# Channel_A.net
KiCad netlist of a schematic drawn in Altium Designer
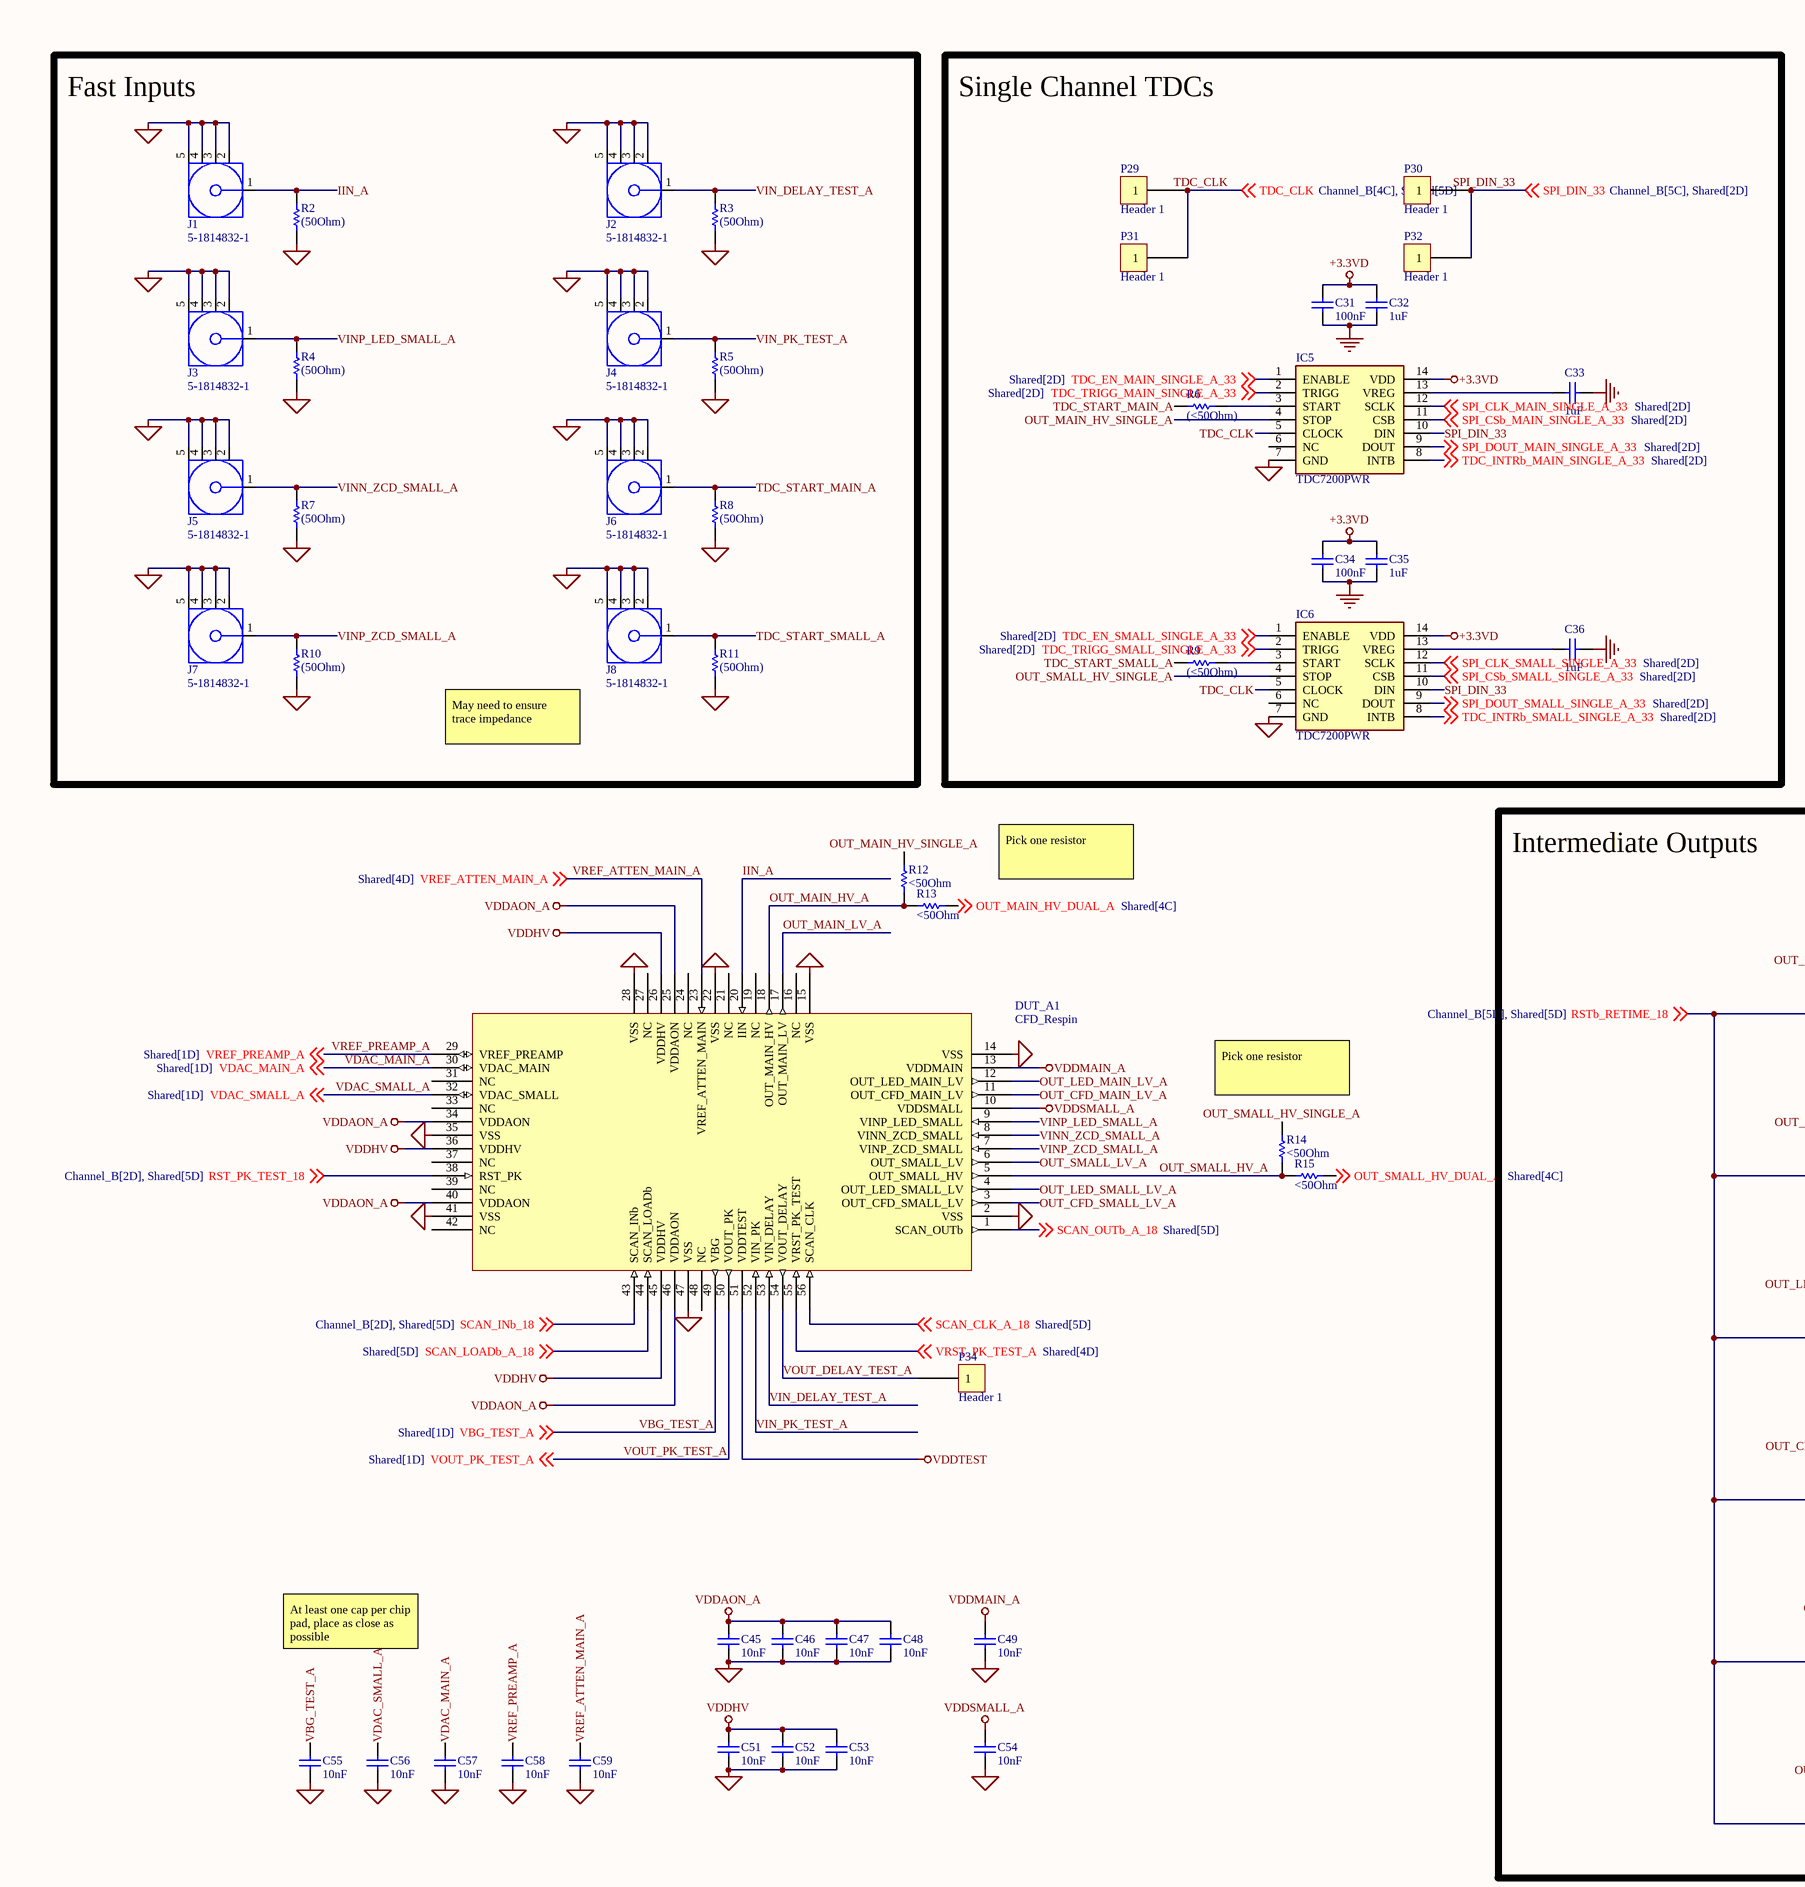
[diagram p0: Channel_A.SchDoc, left]
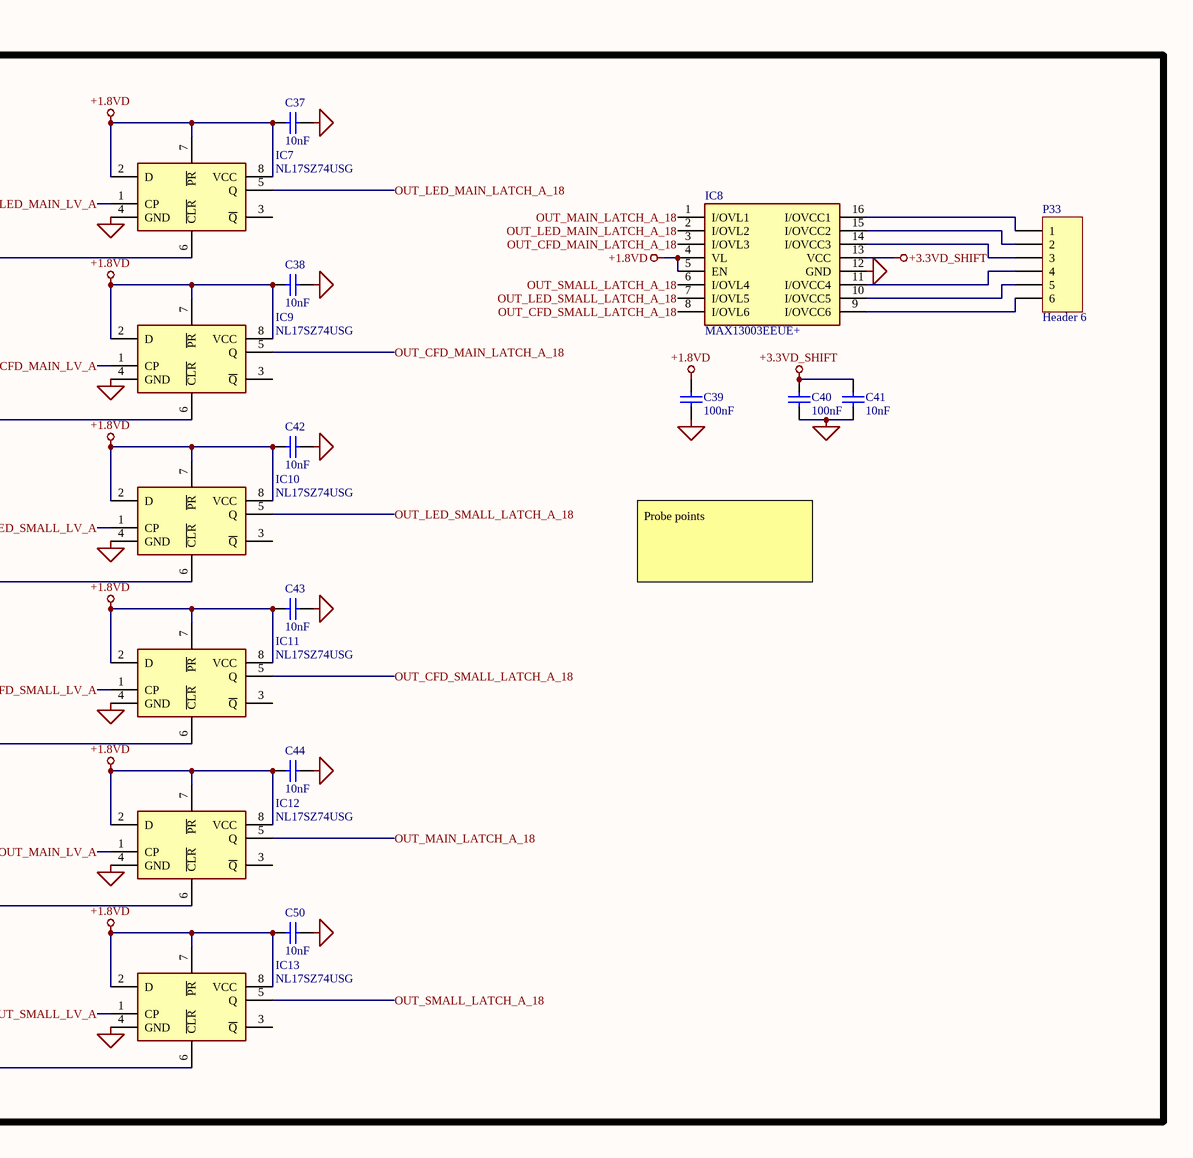
[diagram p1: Channel_A.SchDoc, right]

(export (version "E")
  (design (tool "Eeschema 10.0.6"))
  (components
    (comp (ref "C31")
      (value "100nF")
      (footprint "CAPC1608X90X35ML10T15")
      (description "0603")
      (fields (field (name "MANUFACTURER") "Murata"))
      (libsource (lib "Altium Content Vault") (part "CAP-NP-2"))
    )
    (comp (ref "C32")
      (value "1uF")
      (footprint "CAPC1608X90X35ML10T15")
      (description "0603")
      (fields (field (name "MANUFACTURER") "Murata"))
      (libsource (lib "Altium Content Vault") (part "CAP-NP-2"))
    )
    (comp (ref "C33")
      (value "1uF")
      (footprint "CAPC1608X90X35ML10T15")
      (description "0603")
      (fields (field (name "MANUFACTURER") "Murata"))
      (libsource (lib "Altium Content Vault") (part "CAP-NP-2"))
    )
    (comp (ref "C34")
      (value "100nF")
      (footprint "CAPC1608X90X35ML10T15")
      (description "0603")
      (fields (field (name "MANUFACTURER") "Murata"))
      (libsource (lib "Altium Content Vault") (part "CAP-NP-2"))
    )
    (comp (ref "C35")
      (value "1uF")
      (footprint "CAPC1608X90X35ML10T15")
      (description "0603")
      (fields (field (name "MANUFACTURER") "Murata"))
      (libsource (lib "Altium Content Vault") (part "CAP-NP-2"))
    )
    (comp (ref "C36")
      (value "1uF")
      (footprint "CAPC1608X90X35ML10T15")
      (description "0603")
      (fields (field (name "MANUFACTURER") "Murata"))
      (libsource (lib "Altium Content Vault") (part "CAP-NP-2"))
    )
    (comp (ref "C37")
      (value "10nF")
      (footprint "CAPC1608X90X35ML10T15")
      (description "0603")
      (fields (field (name "MANUFACTURER") "Murata"))
      (libsource (lib "Altium Content Vault") (part "CAP-NP-2"))
    )
    (comp (ref "C38")
      (value "10nF")
      (footprint "CAPC1608X90X35ML10T15")
      (description "0603")
      (fields (field (name "MANUFACTURER") "Murata"))
      (libsource (lib "Altium Content Vault") (part "CAP-NP-2"))
    )
    (comp (ref "C39")
      (value "100nF")
      (footprint "CAPC1608X90X35ML10T15")
      (description "0603")
      (fields (field (name "MANUFACTURER") "Murata"))
      (libsource (lib "Altium Content Vault") (part "CAP-NP-2"))
    )
    (comp (ref "C40")
      (value "100nF")
      (footprint "CAPC1608X90X35ML10T15")
      (description "0603")
      (fields (field (name "MANUFACTURER") "Murata"))
      (libsource (lib "Altium Content Vault") (part "CAP-NP-2"))
    )
    (comp (ref "C41")
      (value "10nF")
      (footprint "CAPC1608X90X35ML10T15")
      (description "0603")
      (fields (field (name "MANUFACTURER") "Murata"))
      (libsource (lib "Altium Content Vault") (part "CAP-NP-2"))
    )
    (comp (ref "C42")
      (value "10nF")
      (footprint "CAPC1608X90X35ML10T15")
      (description "0603")
      (fields (field (name "MANUFACTURER") "Murata"))
      (libsource (lib "Altium Content Vault") (part "CAP-NP-2"))
    )
    (comp (ref "C43")
      (value "10nF")
      (footprint "CAPC1608X90X35ML10T15")
      (description "0603")
      (fields (field (name "MANUFACTURER") "Murata"))
      (libsource (lib "Altium Content Vault") (part "CAP-NP-2"))
    )
    (comp (ref "C44")
      (value "10nF")
      (footprint "CAPC1608X90X35ML10T15")
      (description "0603")
      (fields (field (name "MANUFACTURER") "Murata"))
      (libsource (lib "Altium Content Vault") (part "CAP-NP-2"))
    )
    (comp (ref "C45")
      (value "10nF")
      (footprint "CAPC1608X90X35ML10T15")
      (description "0603")
      (fields (field (name "MANUFACTURER") "Murata"))
      (libsource (lib "Altium Content Vault") (part "CAP-NP-2"))
    )
    (comp (ref "C46")
      (value "10nF")
      (footprint "CAPC1608X90X35ML10T15")
      (description "0603")
      (fields (field (name "MANUFACTURER") "Murata"))
      (libsource (lib "Altium Content Vault") (part "CAP-NP-2"))
    )
    (comp (ref "C47")
      (value "10nF")
      (footprint "CAPC1608X90X35ML10T15")
      (description "0603")
      (fields (field (name "MANUFACTURER") "Murata"))
      (libsource (lib "Altium Content Vault") (part "CAP-NP-2"))
    )
    (comp (ref "C48")
      (value "10nF")
      (footprint "CAPC1608X90X35ML10T15")
      (description "0603")
      (fields (field (name "MANUFACTURER") "Murata"))
      (libsource (lib "Altium Content Vault") (part "CAP-NP-2"))
    )
    (comp (ref "C49")
      (value "10nF")
      (footprint "CAPC1608X90X35ML10T15")
      (description "0603")
      (fields (field (name "MANUFACTURER") "Murata"))
      (libsource (lib "Altium Content Vault") (part "CAP-NP-2"))
    )
    (comp (ref "C50")
      (value "10nF")
      (footprint "CAPC1608X90X35ML10T15")
      (description "0603")
      (fields (field (name "MANUFACTURER") "Murata"))
      (libsource (lib "Altium Content Vault") (part "CAP-NP-2"))
    )
    (comp (ref "C51")
      (value "10nF")
      (footprint "CAPC1608X90X35ML10T15")
      (description "0603")
      (fields (field (name "MANUFACTURER") "Murata"))
      (libsource (lib "Altium Content Vault") (part "CAP-NP-2"))
    )
    (comp (ref "C52")
      (value "10nF")
      (footprint "CAPC1608X90X35ML10T15")
      (description "0603")
      (fields (field (name "MANUFACTURER") "Murata"))
      (libsource (lib "Altium Content Vault") (part "CAP-NP-2"))
    )
    (comp (ref "C53")
      (value "10nF")
      (footprint "CAPC1608X90X35ML10T15")
      (description "0603")
      (fields (field (name "MANUFACTURER") "Murata"))
      (libsource (lib "Altium Content Vault") (part "CAP-NP-2"))
    )
    (comp (ref "C54")
      (value "10nF")
      (footprint "CAPC1608X90X35ML10T15")
      (description "0603")
      (fields (field (name "MANUFACTURER") "Murata"))
      (libsource (lib "Altium Content Vault") (part "CAP-NP-2"))
    )
    (comp (ref "C55")
      (value "10nF")
      (footprint "CAPC1608X90X35ML10T15")
      (description "0603")
      (fields (field (name "MANUFACTURER") "Murata"))
      (libsource (lib "Altium Content Vault") (part "CAP-NP-2"))
    )
    (comp (ref "C56")
      (value "10nF")
      (footprint "CAPC1608X90X35ML10T15")
      (description "0603")
      (fields (field (name "MANUFACTURER") "Murata"))
      (libsource (lib "Altium Content Vault") (part "CAP-NP-2"))
    )
    (comp (ref "C57")
      (value "10nF")
      (footprint "CAPC1608X90X35ML10T15")
      (description "0603")
      (fields (field (name "MANUFACTURER") "Murata"))
      (libsource (lib "Altium Content Vault") (part "CAP-NP-2"))
    )
    (comp (ref "C58")
      (value "10nF")
      (footprint "CAPC1608X90X35ML10T15")
      (description "0603")
      (fields (field (name "MANUFACTURER") "Murata"))
      (libsource (lib "Altium Content Vault") (part "CAP-NP-2"))
    )
    (comp (ref "C59")
      (value "10nF")
      (footprint "CAPC1608X90X35ML10T15")
      (description "0603")
      (fields (field (name "MANUFACTURER") "Murata"))
      (libsource (lib "Altium Content Vault") (part "CAP-NP-2"))
    )
    (comp (ref "DUT_A1")
      (value "CFD_Respin")
      (footprint "QFN50P800X800X80_HS-57N_WIDEVIAS")
      (libsource (lib "intlib") (part "CFD_Respin"))
    )
    (comp (ref "IC5")
      (value "TDC7200PWR")
      (footprint "SamacSys:SOP65P640X120-14N")
      (description "Integrated Circuit")
      (libsource (lib "*") (part "TDC7200PWR"))
    )
    (comp (ref "IC6")
      (value "TDC7200PWR")
      (footprint "SamacSys:SOP65P640X120-14N")
      (description "Integrated Circuit")
      (libsource (lib "*") (part "TDC7200PWR"))
    )
    (comp (ref "IC7")
      (value "NL17SZ74USG")
      (footprint "SamacSys:SOP50P310X90-8N")
      (description "Flip Flops 1.65-5.5V CMOS Single D-Type")
      (libsource (lib "SamacSys") (part "NL17SZ74USG"))
    )
    (comp (ref "IC8")
      (value "MAX13003EEUE+")
      (footprint "SamacSys:SOP65P640X110-16N")
      (description "Integrated Circuit")
      (libsource (lib "*") (part "MAX13003EEUE+"))
    )
    (comp (ref "IC9")
      (value "NL17SZ74USG")
      (footprint "SamacSys:SOP50P310X90-8N")
      (description "Flip Flops 1.65-5.5V CMOS Single D-Type")
      (libsource (lib "SamacSys") (part "NL17SZ74USG"))
    )
    (comp (ref "IC10")
      (value "NL17SZ74USG")
      (footprint "SamacSys:SOP50P310X90-8N")
      (description "Flip Flops 1.65-5.5V CMOS Single D-Type")
      (libsource (lib "SamacSys") (part "NL17SZ74USG"))
    )
    (comp (ref "IC11")
      (value "NL17SZ74USG")
      (footprint "SamacSys:SOP50P310X90-8N")
      (description "Flip Flops 1.65-5.5V CMOS Single D-Type")
      (libsource (lib "SamacSys") (part "NL17SZ74USG"))
    )
    (comp (ref "IC12")
      (value "NL17SZ74USG")
      (footprint "SamacSys:SOP50P310X90-8N")
      (description "Flip Flops 1.65-5.5V CMOS Single D-Type")
      (libsource (lib "SamacSys") (part "NL17SZ74USG"))
    )
    (comp (ref "IC13")
      (value "NL17SZ74USG")
      (footprint "SamacSys:SOP50P310X90-8N")
      (description "Flip Flops 1.65-5.5V CMOS Single D-Type")
      (libsource (lib "SamacSys") (part "NL17SZ74USG"))
    )
    (comp (ref "J1")
      (value "5-1814832-1")
      (footprint "TECO-5-1814832-1_V")
      (fields (field (name "MANUFACTURER") "TE Connectivity"))
      (libsource (lib "Altium Content Vault") (part "CN-S-4F-RF5"))
    )
    (comp (ref "J2")
      (value "5-1814832-1")
      (footprint "TECO-5-1814832-1_V")
      (fields (field (name "MANUFACTURER") "TE Connectivity"))
      (libsource (lib "Altium Content Vault") (part "CN-S-4F-RF5"))
    )
    (comp (ref "J3")
      (value "5-1814832-1")
      (footprint "TECO-5-1814832-1_V")
      (fields (field (name "MANUFACTURER") "TE Connectivity"))
      (libsource (lib "Altium Content Vault") (part "CN-S-4F-RF5"))
    )
    (comp (ref "J4")
      (value "5-1814832-1")
      (footprint "TECO-5-1814832-1_V")
      (fields (field (name "MANUFACTURER") "TE Connectivity"))
      (libsource (lib "Altium Content Vault") (part "CN-S-4F-RF5"))
    )
    (comp (ref "J5")
      (value "5-1814832-1")
      (footprint "TECO-5-1814832-1_V")
      (fields (field (name "MANUFACTURER") "TE Connectivity"))
      (libsource (lib "Altium Content Vault") (part "CN-S-4F-RF5"))
    )
    (comp (ref "J6")
      (value "5-1814832-1")
      (footprint "TECO-5-1814832-1_V")
      (fields (field (name "MANUFACTURER") "TE Connectivity"))
      (libsource (lib "Altium Content Vault") (part "CN-S-4F-RF5"))
    )
    (comp (ref "J7")
      (value "5-1814832-1")
      (footprint "TECO-5-1814832-1_V")
      (fields (field (name "MANUFACTURER") "TE Connectivity"))
      (libsource (lib "Altium Content Vault") (part "CN-S-4F-RF5"))
    )
    (comp (ref "J8")
      (value "5-1814832-1")
      (footprint "TECO-5-1814832-1_V")
      (fields (field (name "MANUFACTURER") "TE Connectivity"))
      (libsource (lib "Altium Content Vault") (part "CN-S-4F-RF5"))
    )
    (comp (ref "P29") (value "Header 1") (footprint "Header1") (libsource (lib "intlib") (part "Header 1")))
    (comp (ref "P30") (value "Header 1") (footprint "Header1") (libsource (lib "intlib") (part "Header 1")))
    (comp (ref "P31") (value "Header 1") (footprint "Header1") (libsource (lib "intlib") (part "Header 1")))
    (comp (ref "P32") (value "Header 1") (footprint "Header1") (libsource (lib "intlib") (part "Header 1")))
    (comp (ref "P33")
      (value "Header 6")
      (footprint "HDR1X6")
      (description "Header, 6-Pin")
      (fields (field (name "PUBLISHER") "Altium Limited"))
      (libsource (lib "Miscellaneous Connectors") (part "Header 6"))
    )
    (comp (ref "P34") (value "Header 1") (footprint "Header1") (libsource (lib "") (part "Header 1_1")))
    (comp (ref "R2")
      (value "(50Ohm)")
      (footprint "RESC1609X50X30NL8T20")
      (description "0603")
      (fields (field (name "MANUFACTURER") "Vishay Semiconductor"))
      (libsource (lib "Altium Content Vault") (part "RES-2"))
    )
    (comp (ref "R3")
      (value "(50Ohm)")
      (footprint "RESC1609X50X30NL8T20")
      (description "0603")
      (fields (field (name "MANUFACTURER") "Vishay Semiconductor"))
      (libsource (lib "Altium Content Vault") (part "RES-2"))
    )
    (comp (ref "R4")
      (value "(50Ohm)")
      (footprint "RESC1609X50X30NL8T20")
      (description "0603")
      (fields (field (name "MANUFACTURER") "Vishay Semiconductor"))
      (libsource (lib "Altium Content Vault") (part "RES-2"))
    )
    (comp (ref "R5")
      (value "(50Ohm)")
      (footprint "RESC1609X50X30NL8T20")
      (description "0603")
      (fields (field (name "MANUFACTURER") "Vishay Semiconductor"))
      (libsource (lib "Altium Content Vault") (part "RES-2"))
    )
    (comp (ref "R6")
      (value "(<50Ohm)")
      (footprint "RESC1609X50X30NL8T20")
      (description "0603")
      (fields (field (name "MANUFACTURER") "Vishay Semiconductor"))
      (libsource (lib "Altium Content Vault") (part "RES-2"))
    )
    (comp (ref "R7")
      (value "(50Ohm)")
      (footprint "RESC1609X50X30NL8T20")
      (description "0603")
      (fields (field (name "MANUFACTURER") "Vishay Semiconductor"))
      (libsource (lib "Altium Content Vault") (part "RES-2"))
    )
    (comp (ref "R8")
      (value "(50Ohm)")
      (footprint "RESC1609X50X30NL8T20")
      (description "0603")
      (fields (field (name "MANUFACTURER") "Vishay Semiconductor"))
      (libsource (lib "Altium Content Vault") (part "RES-2"))
    )
    (comp (ref "R9")
      (value "(<50Ohm)")
      (footprint "RESC1609X50X30NL8T20")
      (description "0603")
      (fields (field (name "MANUFACTURER") "Vishay Semiconductor"))
      (libsource (lib "Altium Content Vault") (part "RES-2"))
    )
    (comp (ref "R10")
      (value "(50Ohm)")
      (footprint "RESC1609X50X30NL8T20")
      (description "0603")
      (fields (field (name "MANUFACTURER") "Vishay Semiconductor"))
      (libsource (lib "Altium Content Vault") (part "RES-2"))
    )
    (comp (ref "R11")
      (value "(50Ohm)")
      (footprint "RESC1609X50X30NL8T20")
      (description "0603")
      (fields (field (name "MANUFACTURER") "Vishay Semiconductor"))
      (libsource (lib "Altium Content Vault") (part "RES-2"))
    )
    (comp (ref "R12")
      (value "<50Ohm")
      (footprint "RESC1609X50X30NL8T20")
      (description "0603")
      (fields (field (name "MANUFACTURER") "Vishay Semiconductor"))
      (libsource (lib "Altium Content Vault") (part "RES-2"))
    )
    (comp (ref "R13")
      (value "<50Ohm")
      (footprint "RESC1609X50X30NL8T20")
      (description "0603")
      (fields (field (name "MANUFACTURER") "Vishay Semiconductor"))
      (libsource (lib "Altium Content Vault") (part "RES-2"))
    )
    (comp (ref "R14")
      (value "<50Ohm")
      (footprint "RESC1609X50X30NL8T20")
      (description "0603")
      (fields (field (name "MANUFACTURER") "Vishay Semiconductor"))
      (libsource (lib "Altium Content Vault") (part "RES-2"))
    )
    (comp (ref "R15")
      (value "<50Ohm")
      (footprint "RESC1609X50X30NL8T20")
      (description "0603")
      (fields (field (name "MANUFACTURER") "Vishay Semiconductor"))
      (libsource (lib "Altium Content Vault") (part "RES-2"))
    )
  )
  (nets
    (net (code "1") (name "+1.8VD") (class "Default")
      (node (ref "C37") (pin "2") (pinfunction "2_2") (pintype "passive"))
      (node (ref "C38") (pin "2") (pinfunction "2_2") (pintype "passive"))
      (node (ref "C39") (pin "2") (pinfunction "2_2") (pintype "passive"))
      (node (ref "C42") (pin "2") (pinfunction "2_2") (pintype "passive"))
      (node (ref "C43") (pin "2") (pinfunction "2_2") (pintype "passive"))
      (node (ref "C44") (pin "2") (pinfunction "2_2") (pintype "passive"))
      (node (ref "C50") (pin "2") (pinfunction "2_2") (pintype "passive"))
      (node (ref "IC10") (pin "2") (pinfunction "D_2") (pintype "passive"))
      (node (ref "IC10") (pin "7") (pinfunction "~{PR}_7") (pintype "passive"))
      (node (ref "IC10") (pin "8") (pinfunction "VCC_8") (pintype "passive"))
      (node (ref "IC11") (pin "2") (pinfunction "D_2") (pintype "passive"))
      (node (ref "IC11") (pin "7") (pinfunction "~{PR}_7") (pintype "passive"))
      (node (ref "IC11") (pin "8") (pinfunction "VCC_8") (pintype "passive"))
      (node (ref "IC12") (pin "2") (pinfunction "D_2") (pintype "passive"))
      (node (ref "IC12") (pin "7") (pinfunction "~{PR}_7") (pintype "passive"))
      (node (ref "IC12") (pin "8") (pinfunction "VCC_8") (pintype "passive"))
      (node (ref "IC13") (pin "2") (pinfunction "D_2") (pintype "passive"))
      (node (ref "IC13") (pin "7") (pinfunction "~{PR}_7") (pintype "passive"))
      (node (ref "IC13") (pin "8") (pinfunction "VCC_8") (pintype "passive"))
      (node (ref "IC7") (pin "2") (pinfunction "D_2") (pintype "passive"))
      (node (ref "IC7") (pin "7") (pinfunction "~{PR}_7") (pintype "passive"))
      (node (ref "IC7") (pin "8") (pinfunction "VCC_8") (pintype "passive"))
      (node (ref "IC8") (pin "4") (pinfunction "VL_4") (pintype "passive"))
      (node (ref "IC8") (pin "5") (pinfunction "EN_5") (pintype "passive"))
      (node (ref "IC9") (pin "2") (pinfunction "D_2") (pintype "passive"))
      (node (ref "IC9") (pin "7") (pinfunction "~{PR}_7") (pintype "passive"))
      (node (ref "IC9") (pin "8") (pinfunction "VCC_8") (pintype "passive"))
    )
    (net (code "2") (name "+3.3VD") (class "Default")
      (node (ref "C31") (pin "1") (pinfunction "1_1") (pintype "passive"))
      (node (ref "C32") (pin "1") (pinfunction "1_1") (pintype "passive"))
      (node (ref "C34") (pin "1") (pinfunction "1_1") (pintype "passive"))
      (node (ref "C35") (pin "1") (pinfunction "1_1") (pintype "passive"))
      (node (ref "IC5") (pin "14") (pinfunction "VDD_14") (pintype "passive"))
      (node (ref "IC6") (pin "14") (pinfunction "VDD_14") (pintype "passive"))
    )
    (net (code "3") (name "+3.3VD_SHIFT") (class "Default")
      (node (ref "C40") (pin "2") (pinfunction "2_2") (pintype "passive"))
      (node (ref "C41") (pin "2") (pinfunction "2_2") (pintype "passive"))
      (node (ref "IC8") (pin "13") (pinfunction "VCC_13") (pintype "passive"))
    )
    (net (code "4") (name "/IIN_A") (class "Default")
      (node (ref "DUT_A1") (pin "20") (pinfunction "IIN_20") (pintype "input"))
      (node (ref "J1") (pin "1") (pinfunction "1_1") (pintype "passive"))
      (node (ref "R2") (pin "2") (pinfunction "2_2") (pintype "passive"))
    )
    (net (code "5") (name "/OUT_CFD_MAIN_LATCH_A_18") (class "Default")
      (node (ref "IC8") (pin "3") (pinfunction "I/OVL3_3") (pintype "passive"))
      (node (ref "IC9") (pin "5") (pinfunction "Q_5") (pintype "passive"))
    )
    (net (code "6") (name "/OUT_CFD_MAIN_LV_A") (class "Default")
      (node (ref "DUT_A1") (pin "11") (pinfunction "OUT_CFD_MAIN_LV_11") (pintype "output"))
      (node (ref "IC9") (pin "1") (pinfunction "CP_1") (pintype "passive"))
    )
    (net (code "7") (name "/OUT_CFD_SMALL_LATCH_A_18") (class "Default")
      (node (ref "IC11") (pin "5") (pinfunction "Q_5") (pintype "passive"))
      (node (ref "IC8") (pin "8") (pinfunction "I/OVL6_8") (pintype "passive"))
    )
    (net (code "8") (name "/OUT_CFD_SMALL_LV_A") (class "Default")
      (node (ref "DUT_A1") (pin "3") (pinfunction "OUT_CFD_SMALL_LV_3") (pintype "output"))
      (node (ref "IC11") (pin "1") (pinfunction "CP_1") (pintype "passive"))
    )
    (net (code "9") (name "/OUT_LED_MAIN_LATCH_A_18") (class "Default")
      (node (ref "IC7") (pin "5") (pinfunction "Q_5") (pintype "passive"))
      (node (ref "IC8") (pin "2") (pinfunction "I/OVL2_2") (pintype "passive"))
    )
    (net (code "10") (name "/OUT_LED_MAIN_LV_A") (class "Default")
      (node (ref "DUT_A1") (pin "12") (pinfunction "OUT_LED_MAIN_LV_12") (pintype "output"))
      (node (ref "IC7") (pin "1") (pinfunction "CP_1") (pintype "passive"))
    )
    (net (code "11") (name "/OUT_LED_SMALL_LATCH_A_18") (class "Default")
      (node (ref "IC10") (pin "5") (pinfunction "Q_5") (pintype "passive"))
      (node (ref "IC8") (pin "7") (pinfunction "I/OVL5_7") (pintype "passive"))
    )
    (net (code "12") (name "/OUT_LED_SMALL_LV_A") (class "Default")
      (node (ref "DUT_A1") (pin "4") (pinfunction "OUT_LED_SMALL_LV_4") (pintype "output"))
      (node (ref "IC10") (pin "1") (pinfunction "CP_1") (pintype "passive"))
    )
    (net (code "13") (name "/OUT_MAIN_HV_A") (class "Default")
      (node (ref "DUT_A1") (pin "18") (pinfunction "OUT_MAIN_HV_18") (pintype "output"))
      (node (ref "R12") (pin "2") (pinfunction "2_2") (pintype "passive"))
      (node (ref "R13") (pin "1") (pinfunction "1_1") (pintype "passive"))
    )
    (net (code "14") (name "/OUT_MAIN_HV_SINGLE_A") (class "Default")
      (node (ref "IC5") (pin "4") (pinfunction "STOP_4") (pintype "passive"))
      (node (ref "R12") (pin "1") (pinfunction "1_1") (pintype "passive"))
    )
    (net (code "15") (name "/OUT_MAIN_LATCH_A_18") (class "Default")
      (node (ref "IC12") (pin "5") (pinfunction "Q_5") (pintype "passive"))
      (node (ref "IC8") (pin "1") (pinfunction "I/OVL1_1") (pintype "passive"))
    )
    (net (code "16") (name "/OUT_MAIN_LV_A") (class "Default")
      (node (ref "DUT_A1") (pin "17") (pinfunction "OUT_MAIN_LV_17") (pintype "output"))
      (node (ref "IC12") (pin "1") (pinfunction "CP_1") (pintype "passive"))
    )
    (net (code "17") (name "/OUT_SMALL_HV_A") (class "Default")
      (node (ref "DUT_A1") (pin "5") (pinfunction "OUT_SMALL_HV_5") (pintype "output"))
      (node (ref "R14") (pin "2") (pinfunction "2_2") (pintype "passive"))
      (node (ref "R15") (pin "1") (pinfunction "1_1") (pintype "passive"))
    )
    (net (code "18") (name "/OUT_SMALL_HV_SINGLE_A") (class "Default")
      (node (ref "IC6") (pin "4") (pinfunction "STOP_4") (pintype "passive"))
      (node (ref "R14") (pin "1") (pinfunction "1_1") (pintype "passive"))
    )
    (net (code "19") (name "/OUT_SMALL_LATCH_A_18") (class "Default")
      (node (ref "IC13") (pin "5") (pinfunction "Q_5") (pintype "passive"))
      (node (ref "IC8") (pin "6") (pinfunction "I/OVL4_6") (pintype "passive"))
    )
    (net (code "20") (name "/OUT_SMALL_LV_A") (class "Default")
      (node (ref "DUT_A1") (pin "6") (pinfunction "OUT_SMALL_LV_6") (pintype "output"))
      (node (ref "IC13") (pin "1") (pinfunction "CP_1") (pintype "passive"))
    )
    (net (code "21") (name "/TDC_START_MAIN_A") (class "Default")
      (node (ref "J6") (pin "1") (pinfunction "1_1") (pintype "passive"))
      (node (ref "R6") (pin "1") (pinfunction "1_1") (pintype "passive"))
      (node (ref "R8") (pin "2") (pinfunction "2_2") (pintype "passive"))
    )
    (net (code "22") (name "/TDC_START_SMALL_A") (class "Default")
      (node (ref "J8") (pin "1") (pinfunction "1_1") (pintype "passive"))
      (node (ref "R11") (pin "2") (pinfunction "2_2") (pintype "passive"))
      (node (ref "R9") (pin "1") (pinfunction "1_1") (pintype "passive"))
    )
    (net (code "23") (name "/VINN_ZCD_SMALL_A") (class "Default")
      (node (ref "DUT_A1") (pin "8") (pinfunction "VINN_ZCD_SMALL_8") (pintype "input"))
      (node (ref "J5") (pin "1") (pinfunction "1_1") (pintype "passive"))
      (node (ref "R7") (pin "2") (pinfunction "2_2") (pintype "passive"))
    )
    (net (code "24") (name "/VINP_LED_SMALL_A") (class "Default")
      (node (ref "DUT_A1") (pin "9") (pinfunction "VINP_LED_SMALL_9") (pintype "input"))
      (node (ref "J3") (pin "1") (pinfunction "1_1") (pintype "passive"))
      (node (ref "R4") (pin "2") (pinfunction "2_2") (pintype "passive"))
    )
    (net (code "25") (name "/VINP_ZCD_SMALL_A") (class "Default")
      (node (ref "DUT_A1") (pin "7") (pinfunction "VINP_ZCD_SMALL_7") (pintype "input"))
      (node (ref "J7") (pin "1") (pinfunction "1_1") (pintype "passive"))
      (node (ref "R10") (pin "2") (pinfunction "2_2") (pintype "passive"))
    )
    (net (code "26") (name "/VIN_DELAY_TEST_A") (class "Default")
      (node (ref "DUT_A1") (pin "53") (pinfunction "VIN_DELAY_53") (pintype "input"))
      (node (ref "J2") (pin "1") (pinfunction "1_1") (pintype "passive"))
      (node (ref "R3") (pin "2") (pinfunction "2_2") (pintype "passive"))
    )
    (net (code "27") (name "/VIN_PK_TEST_A") (class "Default")
      (node (ref "DUT_A1") (pin "52") (pinfunction "VIN_PK_52") (pintype "input"))
      (node (ref "J4") (pin "1") (pinfunction "1_1") (pintype "passive"))
      (node (ref "R5") (pin "2") (pinfunction "2_2") (pintype "passive"))
    )
    (net (code "28") (name "/VOUT_DELAY_TEST_A") (class "Default")
      (node (ref "DUT_A1") (pin "54") (pinfunction "VOUT_DELAY_54") (pintype "output"))
      (node (ref "P34") (pin "1") (pinfunction "1_1") (pintype "passive"))
    )
    (net (code "29") (name "GND") (class "Default")
      (node (ref "C31") (pin "2") (pinfunction "2_2") (pintype "passive"))
      (node (ref "C32") (pin "2") (pinfunction "2_2") (pintype "passive"))
      (node (ref "C33") (pin "2") (pinfunction "2_2") (pintype "passive"))
      (node (ref "C34") (pin "2") (pinfunction "2_2") (pintype "passive"))
      (node (ref "C35") (pin "2") (pinfunction "2_2") (pintype "passive"))
      (node (ref "C36") (pin "2") (pinfunction "2_2") (pintype "passive"))
      (node (ref "C37") (pin "1") (pinfunction "1_1") (pintype "passive"))
      (node (ref "C38") (pin "1") (pinfunction "1_1") (pintype "passive"))
      (node (ref "C39") (pin "1") (pinfunction "1_1") (pintype "passive"))
      (node (ref "C40") (pin "1") (pinfunction "1_1") (pintype "passive"))
      (node (ref "C41") (pin "1") (pinfunction "1_1") (pintype "passive"))
      (node (ref "C42") (pin "1") (pinfunction "1_1") (pintype "passive"))
      (node (ref "C43") (pin "1") (pinfunction "1_1") (pintype "passive"))
      (node (ref "C44") (pin "1") (pinfunction "1_1") (pintype "passive"))
      (node (ref "C45") (pin "1") (pinfunction "1_1") (pintype "passive"))
      (node (ref "C46") (pin "1") (pinfunction "1_1") (pintype "passive"))
      (node (ref "C47") (pin "1") (pinfunction "1_1") (pintype "passive"))
      (node (ref "C48") (pin "1") (pinfunction "1_1") (pintype "passive"))
      (node (ref "C49") (pin "1") (pinfunction "1_1") (pintype "passive"))
      (node (ref "C50") (pin "1") (pinfunction "1_1") (pintype "passive"))
      (node (ref "C51") (pin "1") (pinfunction "1_1") (pintype "passive"))
      (node (ref "C52") (pin "1") (pinfunction "1_1") (pintype "passive"))
      (node (ref "C53") (pin "1") (pinfunction "1_1") (pintype "passive"))
      (node (ref "C54") (pin "1") (pinfunction "1_1") (pintype "passive"))
      (node (ref "C55") (pin "1") (pinfunction "1_1") (pintype "passive"))
      (node (ref "C56") (pin "1") (pinfunction "1_1") (pintype "passive"))
      (node (ref "C57") (pin "1") (pinfunction "1_1") (pintype "passive"))
      (node (ref "C58") (pin "1") (pinfunction "1_1") (pintype "passive"))
      (node (ref "C59") (pin "1") (pinfunction "1_1") (pintype "passive"))
      (node (ref "DUT_A1") (pin "14") (pinfunction "VSS_14") (pintype "power_in"))
      (node (ref "DUT_A1") (pin "15") (pinfunction "VSS_15") (pintype "power_in"))
      (node (ref "DUT_A1") (pin "2") (pinfunction "VSS_2") (pintype "power_in"))
      (node (ref "DUT_A1") (pin "22") (pinfunction "VSS_22") (pintype "power_in"))
      (node (ref "DUT_A1") (pin "28") (pinfunction "VSS_28") (pintype "power_in"))
      (node (ref "DUT_A1") (pin "35") (pinfunction "VSS_35") (pintype "power_in"))
      (node (ref "DUT_A1") (pin "41") (pinfunction "VSS_41") (pintype "power_in"))
      (node (ref "DUT_A1") (pin "47") (pinfunction "VSS_47") (pintype "power_in"))
      (node (ref "IC10") (pin "4") (pinfunction "GND_4") (pintype "passive"))
      (node (ref "IC11") (pin "4") (pinfunction "GND_4") (pintype "passive"))
      (node (ref "IC12") (pin "4") (pinfunction "GND_4") (pintype "passive"))
      (node (ref "IC13") (pin "4") (pinfunction "GND_4") (pintype "passive"))
      (node (ref "IC5") (pin "7") (pinfunction "GND_7") (pintype "passive"))
      (node (ref "IC6") (pin "7") (pinfunction "GND_7") (pintype "passive"))
      (node (ref "IC7") (pin "4") (pinfunction "GND_4") (pintype "passive"))
      (node (ref "IC8") (pin "12") (pinfunction "GND_12") (pintype "passive"))
      (node (ref "IC9") (pin "4") (pinfunction "GND_4") (pintype "passive"))
      (node (ref "J1") (pin "2") (pinfunction "2_2") (pintype "passive"))
      (node (ref "J1") (pin "3") (pinfunction "3_3") (pintype "passive"))
      (node (ref "J1") (pin "4") (pinfunction "4_4") (pintype "passive"))
      (node (ref "J1") (pin "5") (pinfunction "5_5") (pintype "passive"))
      (node (ref "J2") (pin "2") (pinfunction "2_2") (pintype "passive"))
      (node (ref "J2") (pin "3") (pinfunction "3_3") (pintype "passive"))
      (node (ref "J2") (pin "4") (pinfunction "4_4") (pintype "passive"))
      (node (ref "J2") (pin "5") (pinfunction "5_5") (pintype "passive"))
      (node (ref "J3") (pin "2") (pinfunction "2_2") (pintype "passive"))
      (node (ref "J3") (pin "3") (pinfunction "3_3") (pintype "passive"))
      (node (ref "J3") (pin "4") (pinfunction "4_4") (pintype "passive"))
      (node (ref "J3") (pin "5") (pinfunction "5_5") (pintype "passive"))
      (node (ref "J4") (pin "2") (pinfunction "2_2") (pintype "passive"))
      (node (ref "J4") (pin "3") (pinfunction "3_3") (pintype "passive"))
      (node (ref "J4") (pin "4") (pinfunction "4_4") (pintype "passive"))
      (node (ref "J4") (pin "5") (pinfunction "5_5") (pintype "passive"))
      (node (ref "J5") (pin "2") (pinfunction "2_2") (pintype "passive"))
      (node (ref "J5") (pin "3") (pinfunction "3_3") (pintype "passive"))
      (node (ref "J5") (pin "4") (pinfunction "4_4") (pintype "passive"))
      (node (ref "J5") (pin "5") (pinfunction "5_5") (pintype "passive"))
      (node (ref "J6") (pin "2") (pinfunction "2_2") (pintype "passive"))
      (node (ref "J6") (pin "3") (pinfunction "3_3") (pintype "passive"))
      (node (ref "J6") (pin "4") (pinfunction "4_4") (pintype "passive"))
      (node (ref "J6") (pin "5") (pinfunction "5_5") (pintype "passive"))
      (node (ref "J7") (pin "2") (pinfunction "2_2") (pintype "passive"))
      (node (ref "J7") (pin "3") (pinfunction "3_3") (pintype "passive"))
      (node (ref "J7") (pin "4") (pinfunction "4_4") (pintype "passive"))
      (node (ref "J7") (pin "5") (pinfunction "5_5") (pintype "passive"))
      (node (ref "J8") (pin "2") (pinfunction "2_2") (pintype "passive"))
      (node (ref "J8") (pin "3") (pinfunction "3_3") (pintype "passive"))
      (node (ref "J8") (pin "4") (pinfunction "4_4") (pintype "passive"))
      (node (ref "J8") (pin "5") (pinfunction "5_5") (pintype "passive"))
      (node (ref "R10") (pin "1") (pinfunction "1_1") (pintype "passive"))
      (node (ref "R11") (pin "1") (pinfunction "1_1") (pintype "passive"))
      (node (ref "R2") (pin "1") (pinfunction "1_1") (pintype "passive"))
      (node (ref "R3") (pin "1") (pinfunction "1_1") (pintype "passive"))
      (node (ref "R4") (pin "1") (pinfunction "1_1") (pintype "passive"))
      (node (ref "R5") (pin "1") (pinfunction "1_1") (pintype "passive"))
      (node (ref "R7") (pin "1") (pinfunction "1_1") (pintype "passive"))
      (node (ref "R8") (pin "1") (pinfunction "1_1") (pintype "passive"))
    )
    (net (code "30") (name "Net-(IC5-START)") (class "Default")
      (node (ref "IC5") (pin "3") (pinfunction "START_3") (pintype "passive"))
      (node (ref "R6") (pin "2") (pinfunction "2_2") (pintype "passive"))
    )
    (net (code "31") (name "Net-(IC5-VREG)") (class "Default")
      (node (ref "C33") (pin "1") (pinfunction "1_1") (pintype "passive"))
      (node (ref "IC5") (pin "13") (pinfunction "VREG_13") (pintype "passive"))
    )
    (net (code "32") (name "Net-(IC6-START)") (class "Default")
      (node (ref "IC6") (pin "3") (pinfunction "START_3") (pintype "passive"))
      (node (ref "R9") (pin "2") (pinfunction "2_2") (pintype "passive"))
    )
    (net (code "33") (name "Net-(IC6-VREG)") (class "Default")
      (node (ref "C36") (pin "1") (pinfunction "1_1") (pintype "passive"))
      (node (ref "IC6") (pin "13") (pinfunction "VREG_13") (pintype "passive"))
    )
    (net (code "34") (name "Net-(IC8-I{slash}OVCC1)") (class "Default")
      (node (ref "IC8") (pin "16") (pinfunction "I/OVCC1_16") (pintype "passive"))
      (node (ref "P33") (pin "1") (pinfunction "1_1") (pintype "passive"))
    )
    (net (code "35") (name "Net-(IC8-I{slash}OVCC2)") (class "Default")
      (node (ref "IC8") (pin "15") (pinfunction "I/OVCC2_15") (pintype "passive"))
      (node (ref "P33") (pin "2") (pinfunction "2_2") (pintype "passive"))
    )
    (net (code "36") (name "Net-(IC8-I{slash}OVCC3)") (class "Default")
      (node (ref "IC8") (pin "14") (pinfunction "I/OVCC3_14") (pintype "passive"))
      (node (ref "P33") (pin "3") (pinfunction "3_3") (pintype "passive"))
    )
    (net (code "37") (name "Net-(IC8-I{slash}OVCC4)") (class "Default")
      (node (ref "IC8") (pin "11") (pinfunction "I/OVCC4_11") (pintype "passive"))
      (node (ref "P33") (pin "4") (pinfunction "4_4") (pintype "passive"))
    )
    (net (code "38") (name "Net-(IC8-I{slash}OVCC5)") (class "Default")
      (node (ref "IC8") (pin "10") (pinfunction "I/OVCC5_10") (pintype "passive"))
      (node (ref "P33") (pin "5") (pinfunction "5_5") (pintype "passive"))
    )
    (net (code "39") (name "Net-(IC8-I{slash}OVCC6)") (class "Default")
      (node (ref "IC8") (pin "9") (pinfunction "I/OVCC6_9") (pintype "passive"))
      (node (ref "P33") (pin "6") (pinfunction "6_6") (pintype "passive"))
    )
    (net (code "40") (name "OUT_MAIN_HV_DUAL_A") (class "Default")
      (node (ref "R13") (pin "2") (pinfunction "2_2") (pintype "passive"))
    )
    (net (code "41") (name "OUT_SMALL_HV_DUAL_A") (class "Default")
      (node (ref "R15") (pin "2") (pinfunction "2_2") (pintype "passive"))
    )
    (net (code "42") (name "RST_PK_TEST_18") (class "Default")
      (node (ref "DUT_A1") (pin "38") (pinfunction "RST_PK_38") (pintype "input"))
    )
    (net (code "43") (name "RSTb_RETIME_18") (class "Default")
      (node (ref "IC10") (pin "6") (pinfunction "~{CLR}_6") (pintype "passive"))
      (node (ref "IC11") (pin "6") (pinfunction "~{CLR}_6") (pintype "passive"))
      (node (ref "IC12") (pin "6") (pinfunction "~{CLR}_6") (pintype "passive"))
      (node (ref "IC13") (pin "6") (pinfunction "~{CLR}_6") (pintype "passive"))
      (node (ref "IC7") (pin "6") (pinfunction "~{CLR}_6") (pintype "passive"))
      (node (ref "IC9") (pin "6") (pinfunction "~{CLR}_6") (pintype "passive"))
    )
    (net (code "44") (name "SCAN_CLK_A_18") (class "Default")
      (node (ref "DUT_A1") (pin "56") (pinfunction "SCAN_CLK_56") (pintype "input"))
    )
    (net (code "45") (name "SCAN_INb_18") (class "Default")
      (node (ref "DUT_A1") (pin "43") (pinfunction "SCAN_INb_43") (pintype "input"))
    )
    (net (code "46") (name "SCAN_LOADb_A_18") (class "Default")
      (node (ref "DUT_A1") (pin "44") (pinfunction "SCAN_LOADb_44") (pintype "input"))
    )
    (net (code "47") (name "SCAN_OUTb_A_18") (class "Default")
      (node (ref "DUT_A1") (pin "1") (pinfunction "SCAN_OUTb_1") (pintype "output"))
    )
    (net (code "48") (name "SPI_CLK_MAIN_SINGLE_A_33") (class "Default")
      (node (ref "IC5") (pin "12") (pinfunction "SCLK_12") (pintype "passive"))
    )
    (net (code "49") (name "SPI_CLK_SMALL_SINGLE_A_33") (class "Default")
      (node (ref "IC6") (pin "12") (pinfunction "SCLK_12") (pintype "passive"))
    )
    (net (code "50") (name "SPI_CSb_MAIN_SINGLE_A_33") (class "Default")
      (node (ref "IC5") (pin "11") (pinfunction "CSB_11") (pintype "passive"))
    )
    (net (code "51") (name "SPI_CSb_SMALL_SINGLE_A_33") (class "Default")
      (node (ref "IC6") (pin "11") (pinfunction "CSB_11") (pintype "passive"))
    )
    (net (code "52") (name "SPI_DIN_33") (class "Default")
      (node (ref "IC5") (pin "10") (pinfunction "DIN_10") (pintype "passive"))
      (node (ref "IC6") (pin "10") (pinfunction "DIN_10") (pintype "passive"))
      (node (ref "P30") (pin "1") (pinfunction "1_1") (pintype "passive"))
      (node (ref "P32") (pin "1") (pinfunction "1_1") (pintype "passive"))
    )
    (net (code "53") (name "SPI_DOUT_MAIN_SINGLE_A_33") (class "Default")
      (node (ref "IC5") (pin "9") (pinfunction "DOUT_9") (pintype "passive"))
    )
    (net (code "54") (name "SPI_DOUT_SMALL_SINGLE_A_33") (class "Default")
      (node (ref "IC6") (pin "9") (pinfunction "DOUT_9") (pintype "passive"))
    )
    (net (code "55") (name "TDC_CLK") (class "Default")
      (node (ref "IC5") (pin "5") (pinfunction "CLOCK_5") (pintype "passive"))
      (node (ref "IC6") (pin "5") (pinfunction "CLOCK_5") (pintype "passive"))
      (node (ref "P29") (pin "1") (pinfunction "1_1") (pintype "passive"))
      (node (ref "P31") (pin "1") (pinfunction "1_1") (pintype "passive"))
    )
    (net (code "56") (name "TDC_EN_MAIN_SINGLE_A_33") (class "Default")
      (node (ref "IC5") (pin "1") (pinfunction "ENABLE_1") (pintype "passive"))
    )
    (net (code "57") (name "TDC_EN_SMALL_SINGLE_A_33") (class "Default")
      (node (ref "IC6") (pin "1") (pinfunction "ENABLE_1") (pintype "passive"))
    )
    (net (code "58") (name "TDC_INTRb_MAIN_SINGLE_A_33") (class "Default")
      (node (ref "IC5") (pin "8") (pinfunction "INTB_8") (pintype "passive"))
    )
    (net (code "59") (name "TDC_INTRb_SMALL_SINGLE_A_33") (class "Default")
      (node (ref "IC6") (pin "8") (pinfunction "INTB_8") (pintype "passive"))
    )
    (net (code "60") (name "TDC_TRIGG_MAIN_SINGLE_A_33") (class "Default")
      (node (ref "IC5") (pin "2") (pinfunction "TRIGG_2") (pintype "passive"))
    )
    (net (code "61") (name "TDC_TRIGG_SMALL_SINGLE_A_33") (class "Default")
      (node (ref "IC6") (pin "2") (pinfunction "TRIGG_2") (pintype "passive"))
    )
    (net (code "62") (name "VBG_TEST_A") (class "Default")
      (node (ref "C55") (pin "2") (pinfunction "2_2") (pintype "passive"))
      (node (ref "DUT_A1") (pin "49") (pinfunction "VBG_49") (pintype "output"))
    )
    (net (code "63") (name "VDAC_MAIN_A") (class "Default")
      (node (ref "C57") (pin "2") (pinfunction "2_2") (pintype "passive"))
      (node (ref "DUT_A1") (pin "30") (pinfunction "VDAC_MAIN_30") (pintype "bidirectional"))
    )
    (net (code "64") (name "VDAC_SMALL_A") (class "Default")
      (node (ref "C56") (pin "2") (pinfunction "2_2") (pintype "passive"))
      (node (ref "DUT_A1") (pin "32") (pinfunction "VDAC_SMALL_32") (pintype "bidirectional"))
    )
    (net (code "65") (name "VDDAON_A") (class "Default")
      (node (ref "C45") (pin "2") (pinfunction "2_2") (pintype "passive"))
      (node (ref "C46") (pin "2") (pinfunction "2_2") (pintype "passive"))
      (node (ref "C47") (pin "2") (pinfunction "2_2") (pintype "passive"))
      (node (ref "C48") (pin "2") (pinfunction "2_2") (pintype "passive"))
      (node (ref "DUT_A1") (pin "25") (pinfunction "VDDAON_25") (pintype "power_in"))
      (node (ref "DUT_A1") (pin "34") (pinfunction "VDDAON_34") (pintype "power_in"))
      (node (ref "DUT_A1") (pin "40") (pinfunction "VDDAON_40") (pintype "power_in"))
      (node (ref "DUT_A1") (pin "46") (pinfunction "VDDAON_46") (pintype "power_in"))
    )
    (net (code "66") (name "VDDHV") (class "Default")
      (node (ref "C51") (pin "2") (pinfunction "2_2") (pintype "passive"))
      (node (ref "C52") (pin "2") (pinfunction "2_2") (pintype "passive"))
      (node (ref "C53") (pin "2") (pinfunction "2_2") (pintype "passive"))
      (node (ref "DUT_A1") (pin "26") (pinfunction "VDDHV_26") (pintype "power_in"))
      (node (ref "DUT_A1") (pin "36") (pinfunction "VDDHV_36") (pintype "power_in"))
      (node (ref "DUT_A1") (pin "45") (pinfunction "VDDHV_45") (pintype "power_in"))
    )
    (net (code "67") (name "VDDMAIN_A") (class "Default")
      (node (ref "C49") (pin "2") (pinfunction "2_2") (pintype "passive"))
      (node (ref "DUT_A1") (pin "13") (pinfunction "VDDMAIN_13") (pintype "power_in"))
    )
    (net (code "68") (name "VDDSMALL_A") (class "Default")
      (node (ref "C54") (pin "2") (pinfunction "2_2") (pintype "passive"))
      (node (ref "DUT_A1") (pin "10") (pinfunction "VDDSMALL_10") (pintype "power_in"))
    )
    (net (code "69") (name "VDDTEST") (class "Default")
      (node (ref "DUT_A1") (pin "51") (pinfunction "VDDTEST_51") (pintype "power_in"))
    )
    (net (code "70") (name "VOUT_PK_TEST_A") (class "Default")
      (node (ref "DUT_A1") (pin "50") (pinfunction "VOUT_PK_50") (pintype "output"))
    )
    (net (code "71") (name "VREF_ATTEN_MAIN_A") (class "Default")
      (node (ref "C59") (pin "2") (pinfunction "2_2") (pintype "passive"))
      (node (ref "DUT_A1") (pin "23") (pinfunction "VREF_ATTEN_MAIN_23") (pintype "input"))
    )
    (net (code "72") (name "VREF_PREAMP_A") (class "Default")
      (node (ref "C58") (pin "2") (pinfunction "2_2") (pintype "passive"))
      (node (ref "DUT_A1") (pin "29") (pinfunction "VREF_PREAMP_29") (pintype "bidirectional"))
    )
    (net (code "73") (name "VRST_PK_TEST_A") (class "Default")
      (node (ref "DUT_A1") (pin "55") (pinfunction "VRST_PK_TEST_55") (pintype "input"))
    )
    (net (code "74") (name "unconnected-(DUT_A1-NC-Pad16)") (class "Default")
      (node (ref "DUT_A1") (pin "16") (pinfunction "NC_16") (pintype "passive"))
    )
    (net (code "75") (name "unconnected-(DUT_A1-NC-Pad19)") (class "Default")
      (node (ref "DUT_A1") (pin "19") (pinfunction "NC_19") (pintype "passive"))
    )
    (net (code "76") (name "unconnected-(DUT_A1-NC-Pad21)") (class "Default")
      (node (ref "DUT_A1") (pin "21") (pinfunction "NC_21") (pintype "passive"))
    )
    (net (code "77") (name "unconnected-(DUT_A1-NC-Pad24)") (class "Default")
      (node (ref "DUT_A1") (pin "24") (pinfunction "NC_24") (pintype "passive"))
    )
    (net (code "78") (name "unconnected-(DUT_A1-NC-Pad27)") (class "Default")
      (node (ref "DUT_A1") (pin "27") (pinfunction "NC_27") (pintype "passive"))
    )
    (net (code "79") (name "unconnected-(DUT_A1-NC-Pad31)") (class "Default")
      (node (ref "DUT_A1") (pin "31") (pinfunction "NC_31") (pintype "passive"))
    )
    (net (code "80") (name "unconnected-(DUT_A1-NC-Pad33)") (class "Default")
      (node (ref "DUT_A1") (pin "33") (pinfunction "NC_33") (pintype "passive"))
    )
    (net (code "81") (name "unconnected-(DUT_A1-NC-Pad37)") (class "Default")
      (node (ref "DUT_A1") (pin "37") (pinfunction "NC_37") (pintype "passive"))
    )
    (net (code "82") (name "unconnected-(DUT_A1-NC-Pad39)") (class "Default")
      (node (ref "DUT_A1") (pin "39") (pinfunction "NC_39") (pintype "passive"))
    )
    (net (code "83") (name "unconnected-(DUT_A1-NC-Pad42)") (class "Default")
      (node (ref "DUT_A1") (pin "42") (pinfunction "NC_42") (pintype "passive"))
    )
    (net (code "84") (name "unconnected-(DUT_A1-NC-Pad48)") (class "Default")
      (node (ref "DUT_A1") (pin "48") (pinfunction "NC_48") (pintype "passive"))
    )
    (net (code "85") (name "unconnected-(IC5-NC-Pad6)") (class "Default")
      (node (ref "IC5") (pin "6") (pinfunction "NC_6") (pintype "passive"))
    )
    (net (code "86") (name "unconnected-(IC6-NC-Pad6)") (class "Default")
      (node (ref "IC6") (pin "6") (pinfunction "NC_6") (pintype "passive"))
    )
    (net (code "87") (name "unconnected-(IC7-~{Q}-Pad3)") (class "Default")
      (node (ref "IC7") (pin "3") (pinfunction "~{Q}_3") (pintype "passive"))
    )
    (net (code "88") (name "unconnected-(IC9-~{Q}-Pad3)") (class "Default")
      (node (ref "IC9") (pin "3") (pinfunction "~{Q}_3") (pintype "passive"))
    )
    (net (code "89") (name "unconnected-(IC10-~{Q}-Pad3)") (class "Default")
      (node (ref "IC10") (pin "3") (pinfunction "~{Q}_3") (pintype "passive"))
    )
    (net (code "90") (name "unconnected-(IC11-~{Q}-Pad3)") (class "Default")
      (node (ref "IC11") (pin "3") (pinfunction "~{Q}_3") (pintype "passive"))
    )
    (net (code "91") (name "unconnected-(IC12-~{Q}-Pad3)") (class "Default")
      (node (ref "IC12") (pin "3") (pinfunction "~{Q}_3") (pintype "passive"))
    )
    (net (code "92") (name "unconnected-(IC13-~{Q}-Pad3)") (class "Default")
      (node (ref "IC13") (pin "3") (pinfunction "~{Q}_3") (pintype "passive"))
    )
  )
)
